# Shield-Proteco.net
KiCad netlist of a schematic drawn in EAGLE
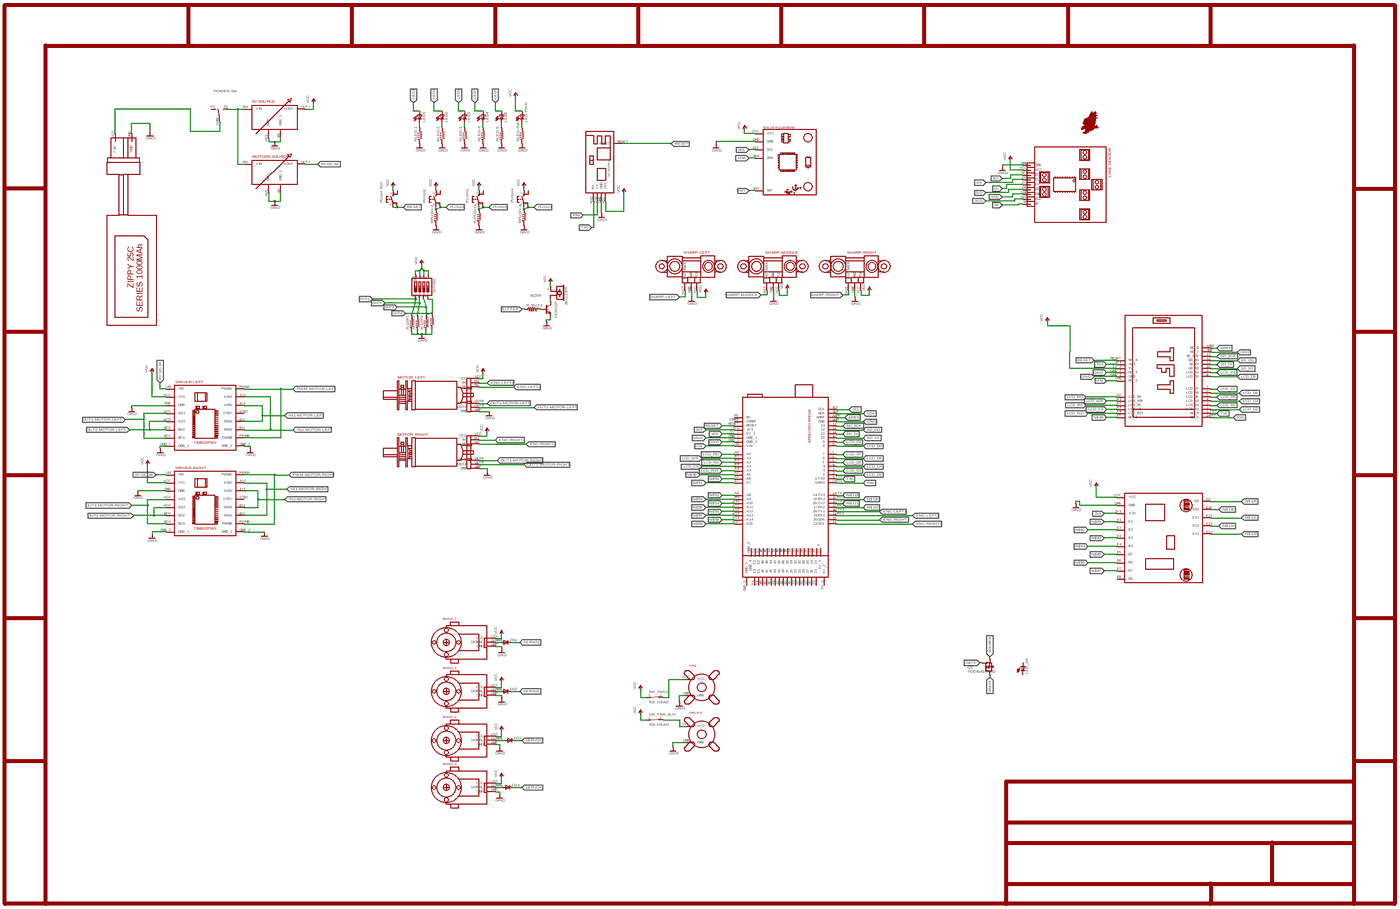
[diagram p0: schematic, sheet 1, overview]
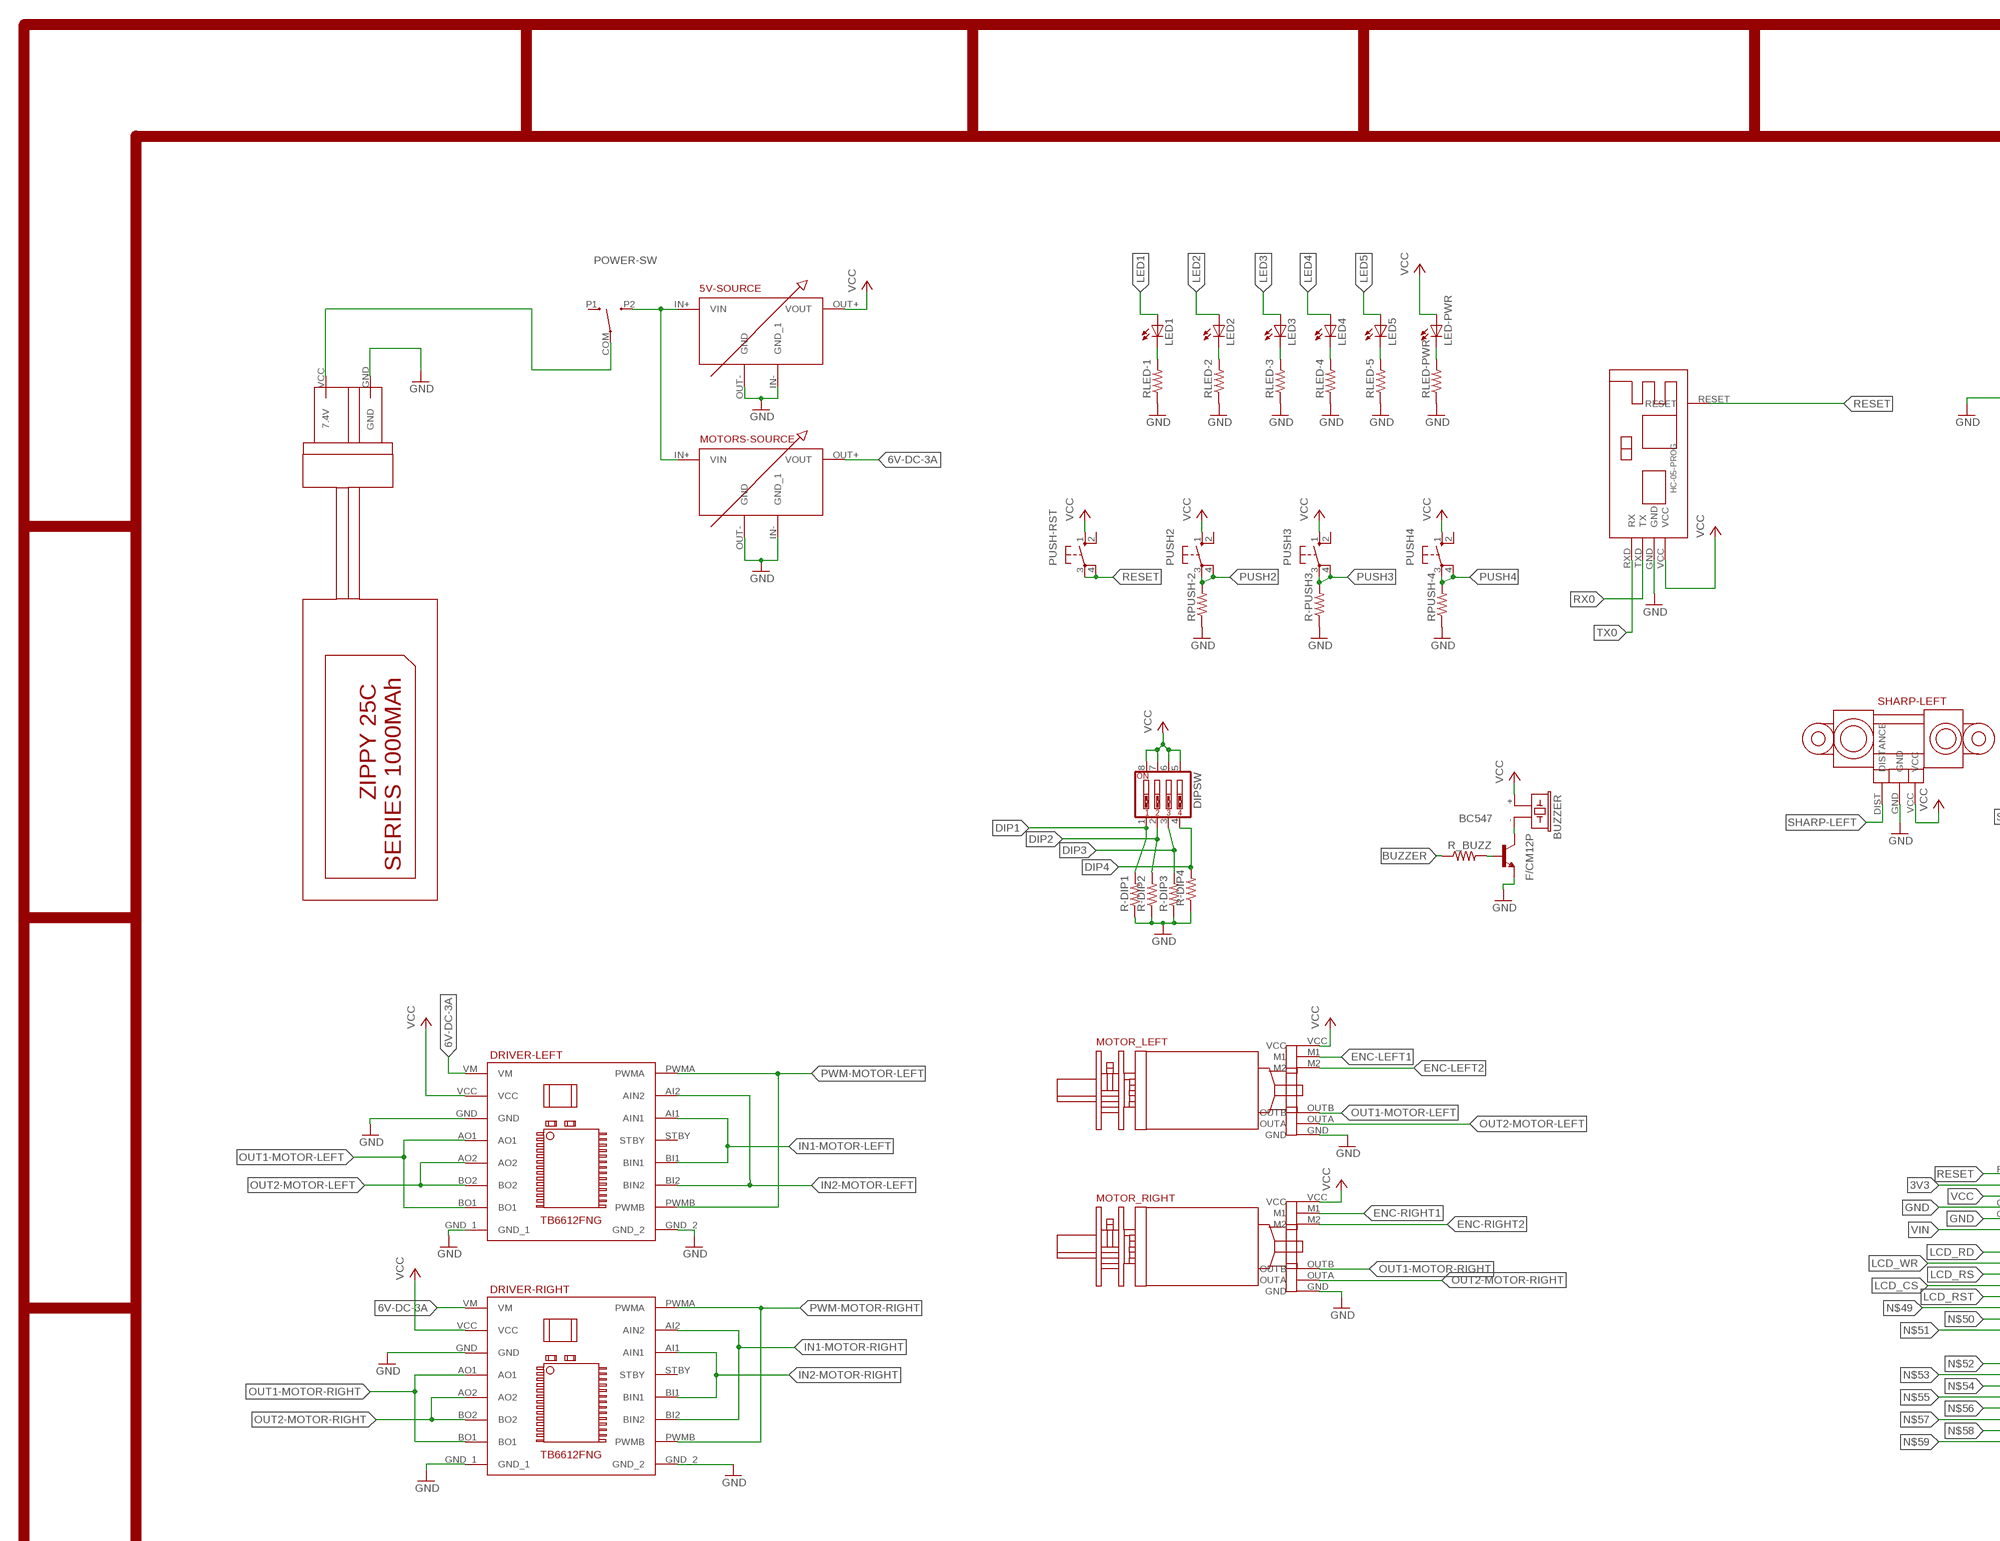
[diagram p1: schematic, sheet 1, part 1 of 4]
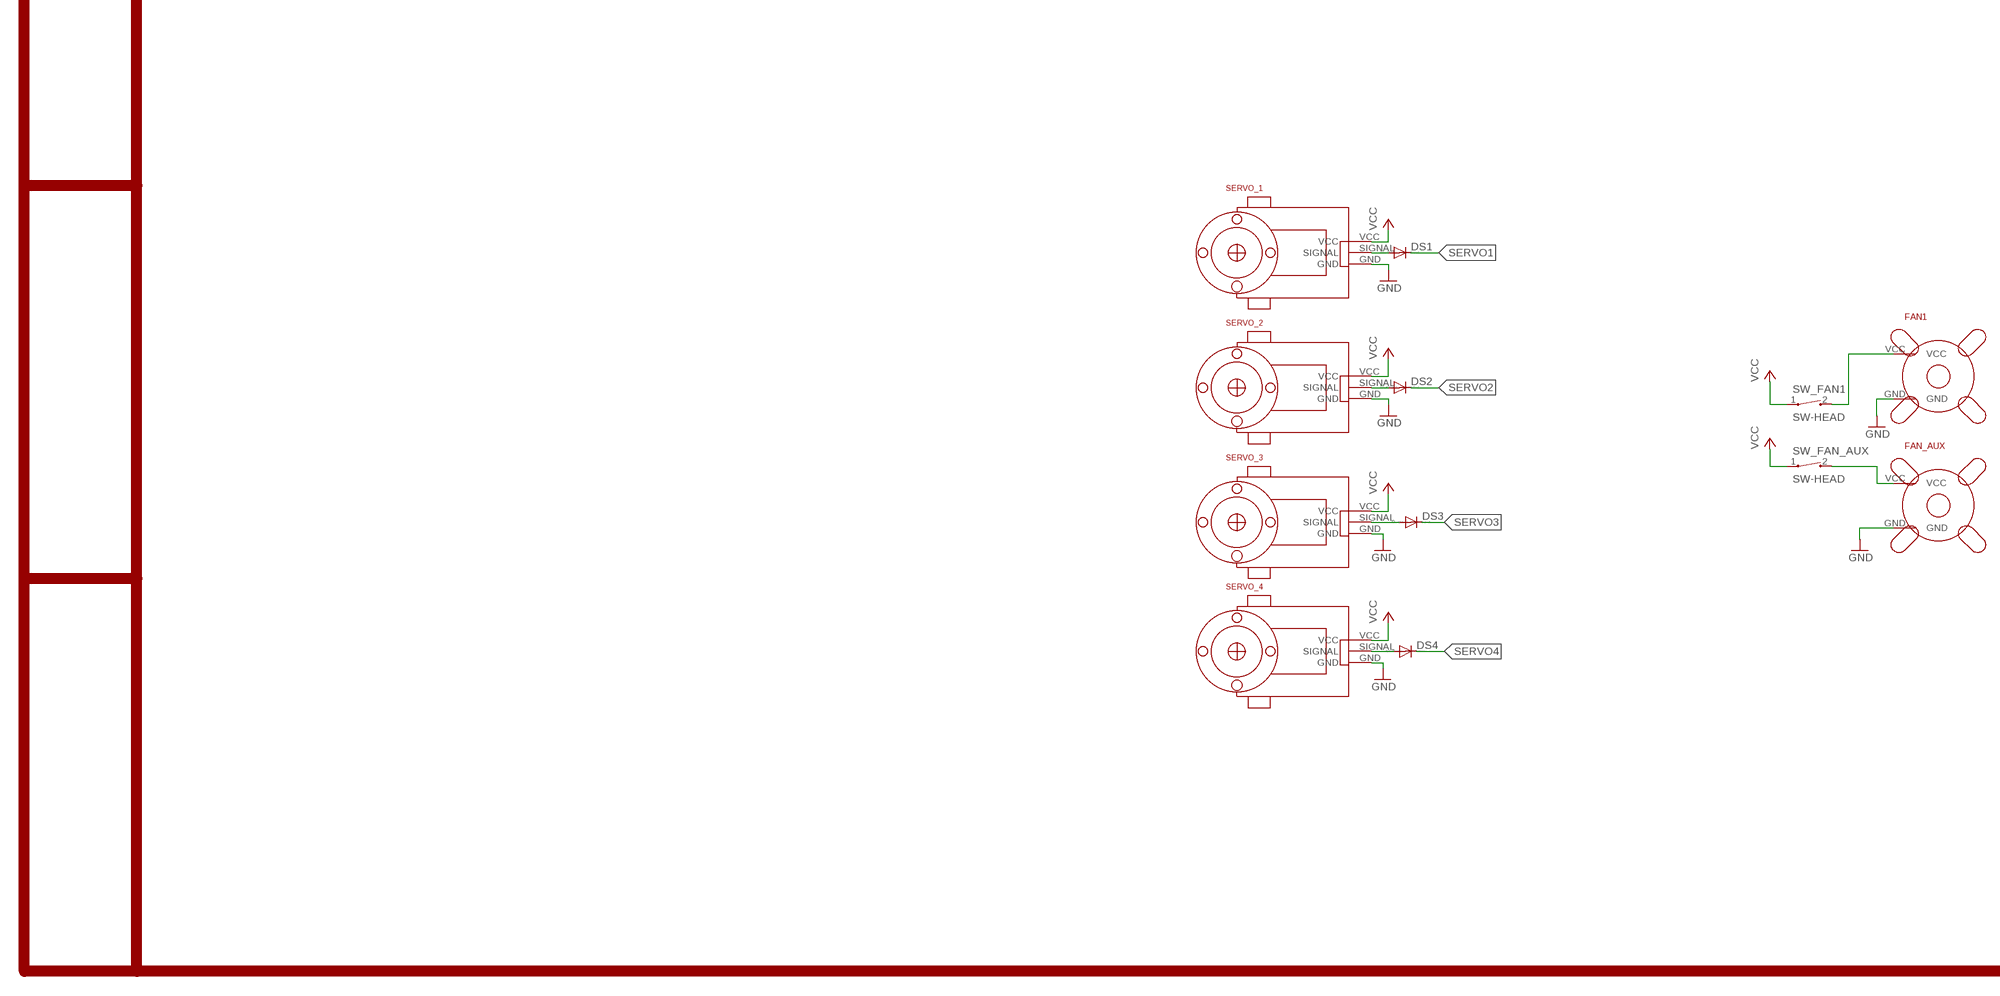
[diagram p2: schematic, sheet 1, part 2 of 4]
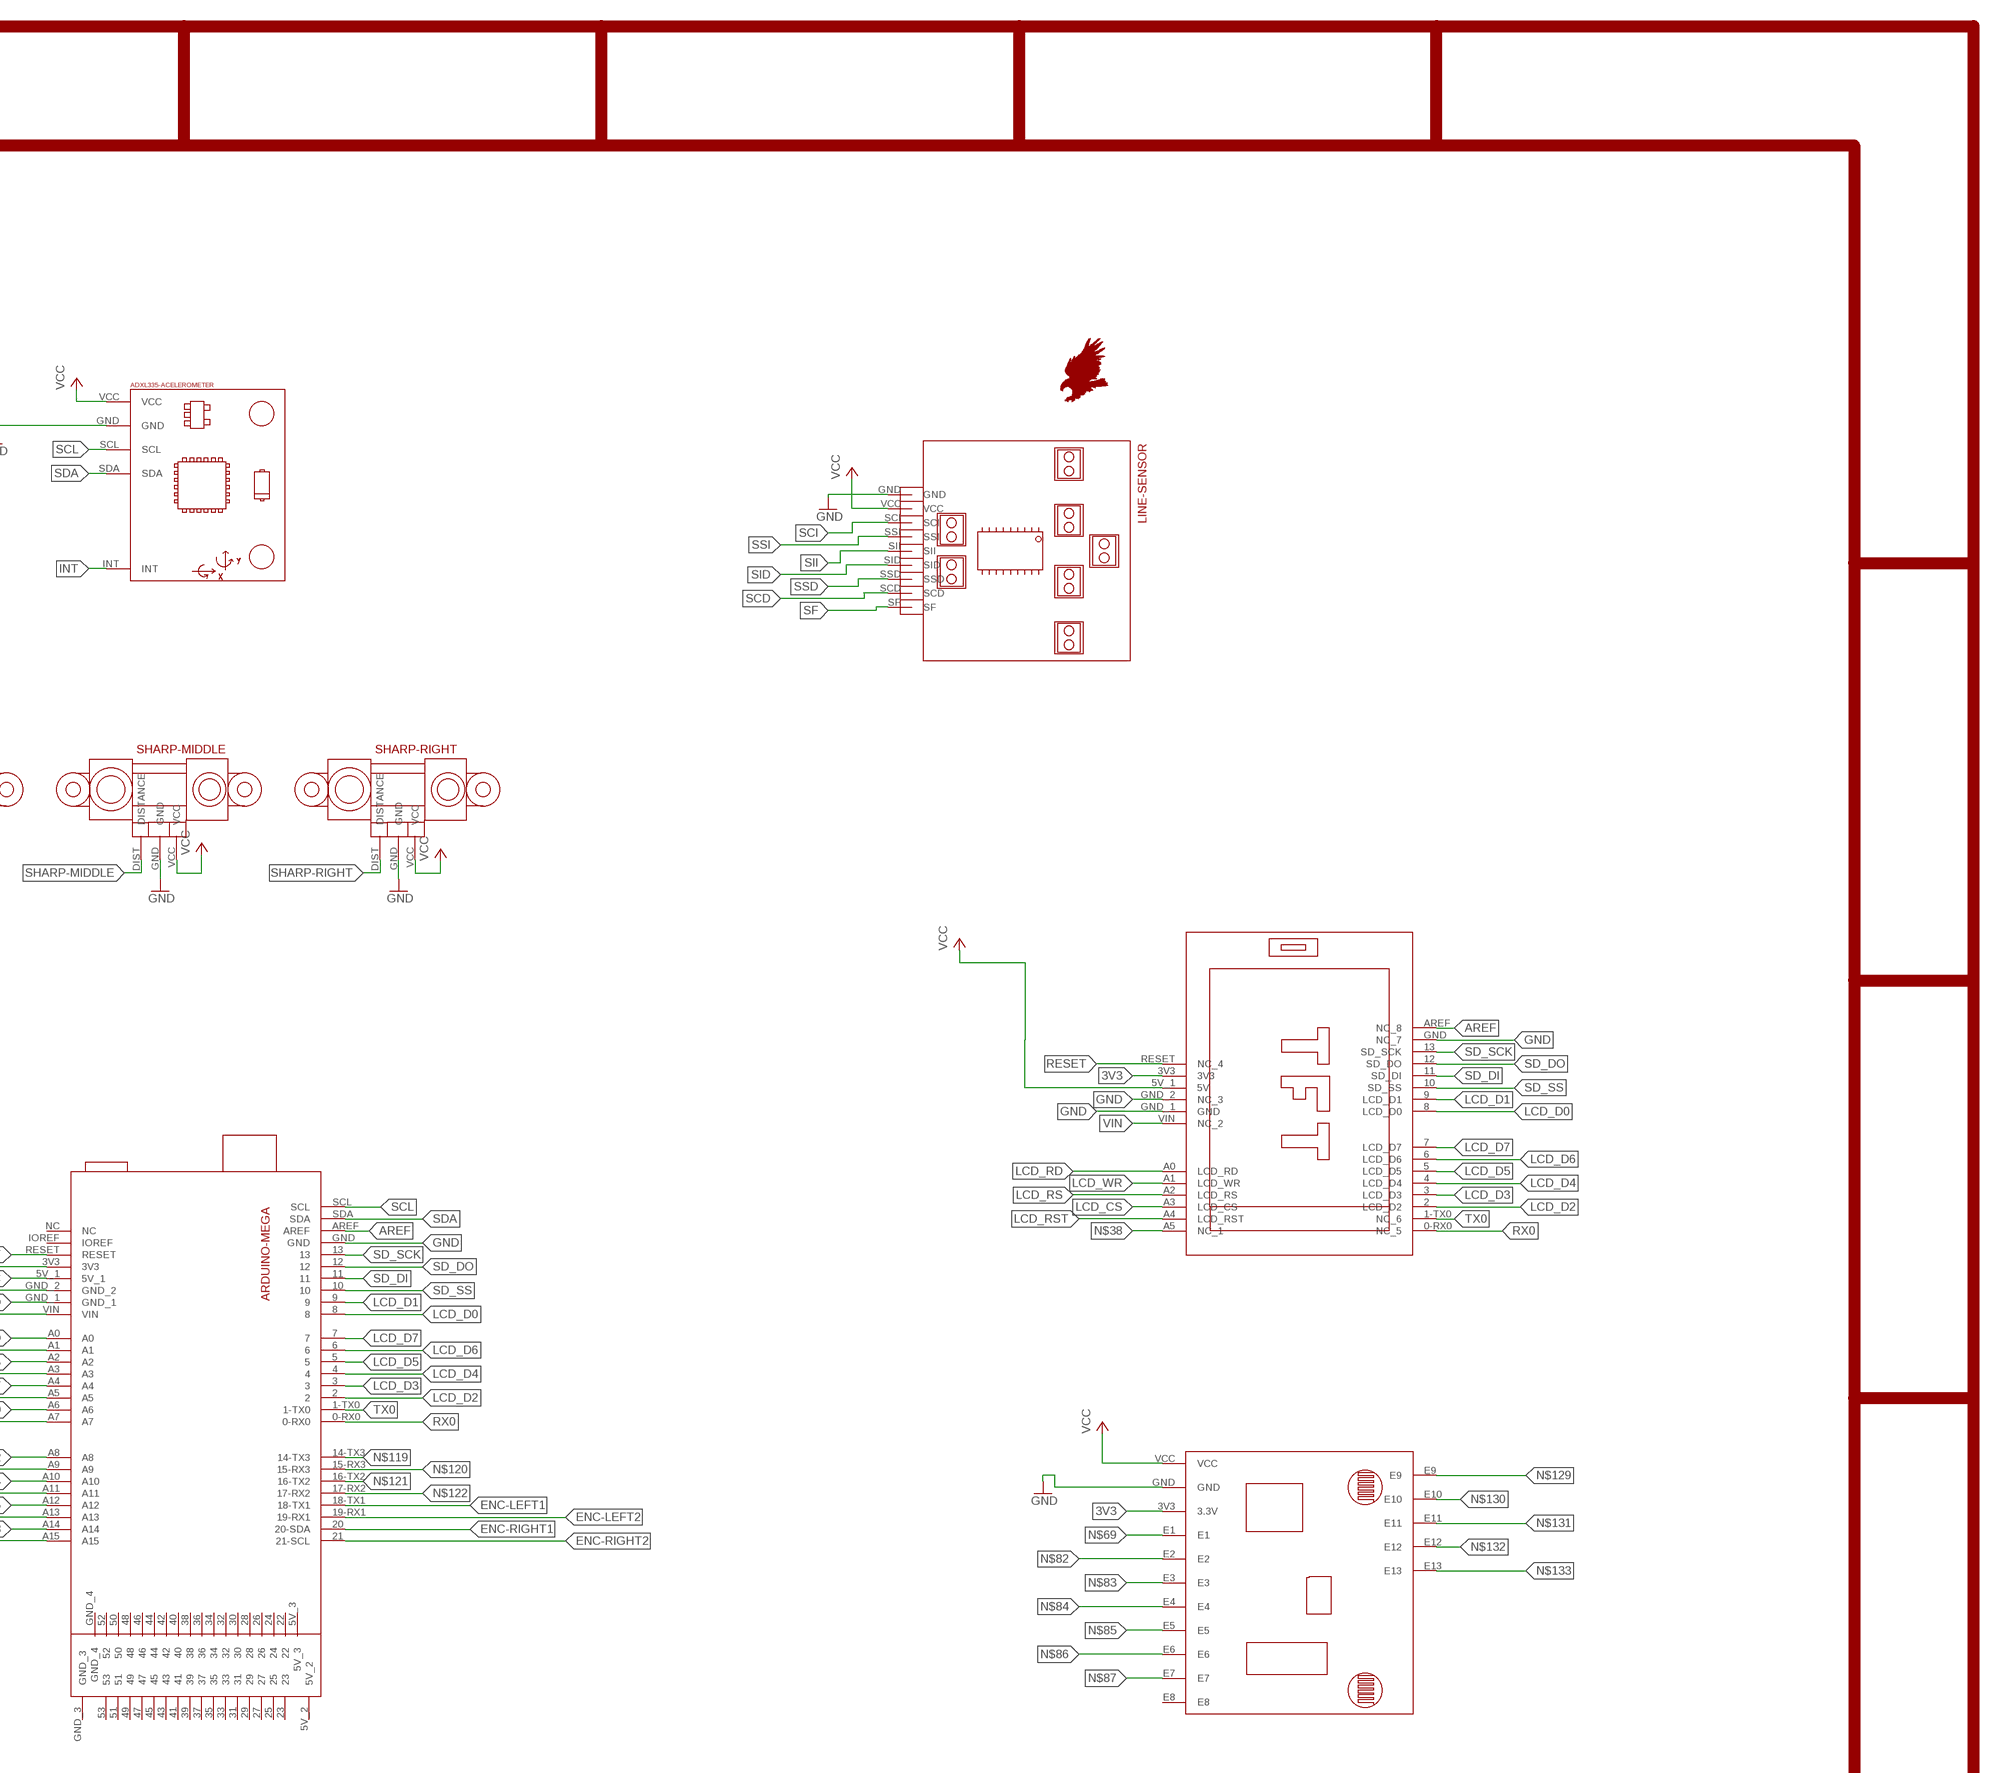
[diagram p3: schematic, sheet 1, part 3 of 4]
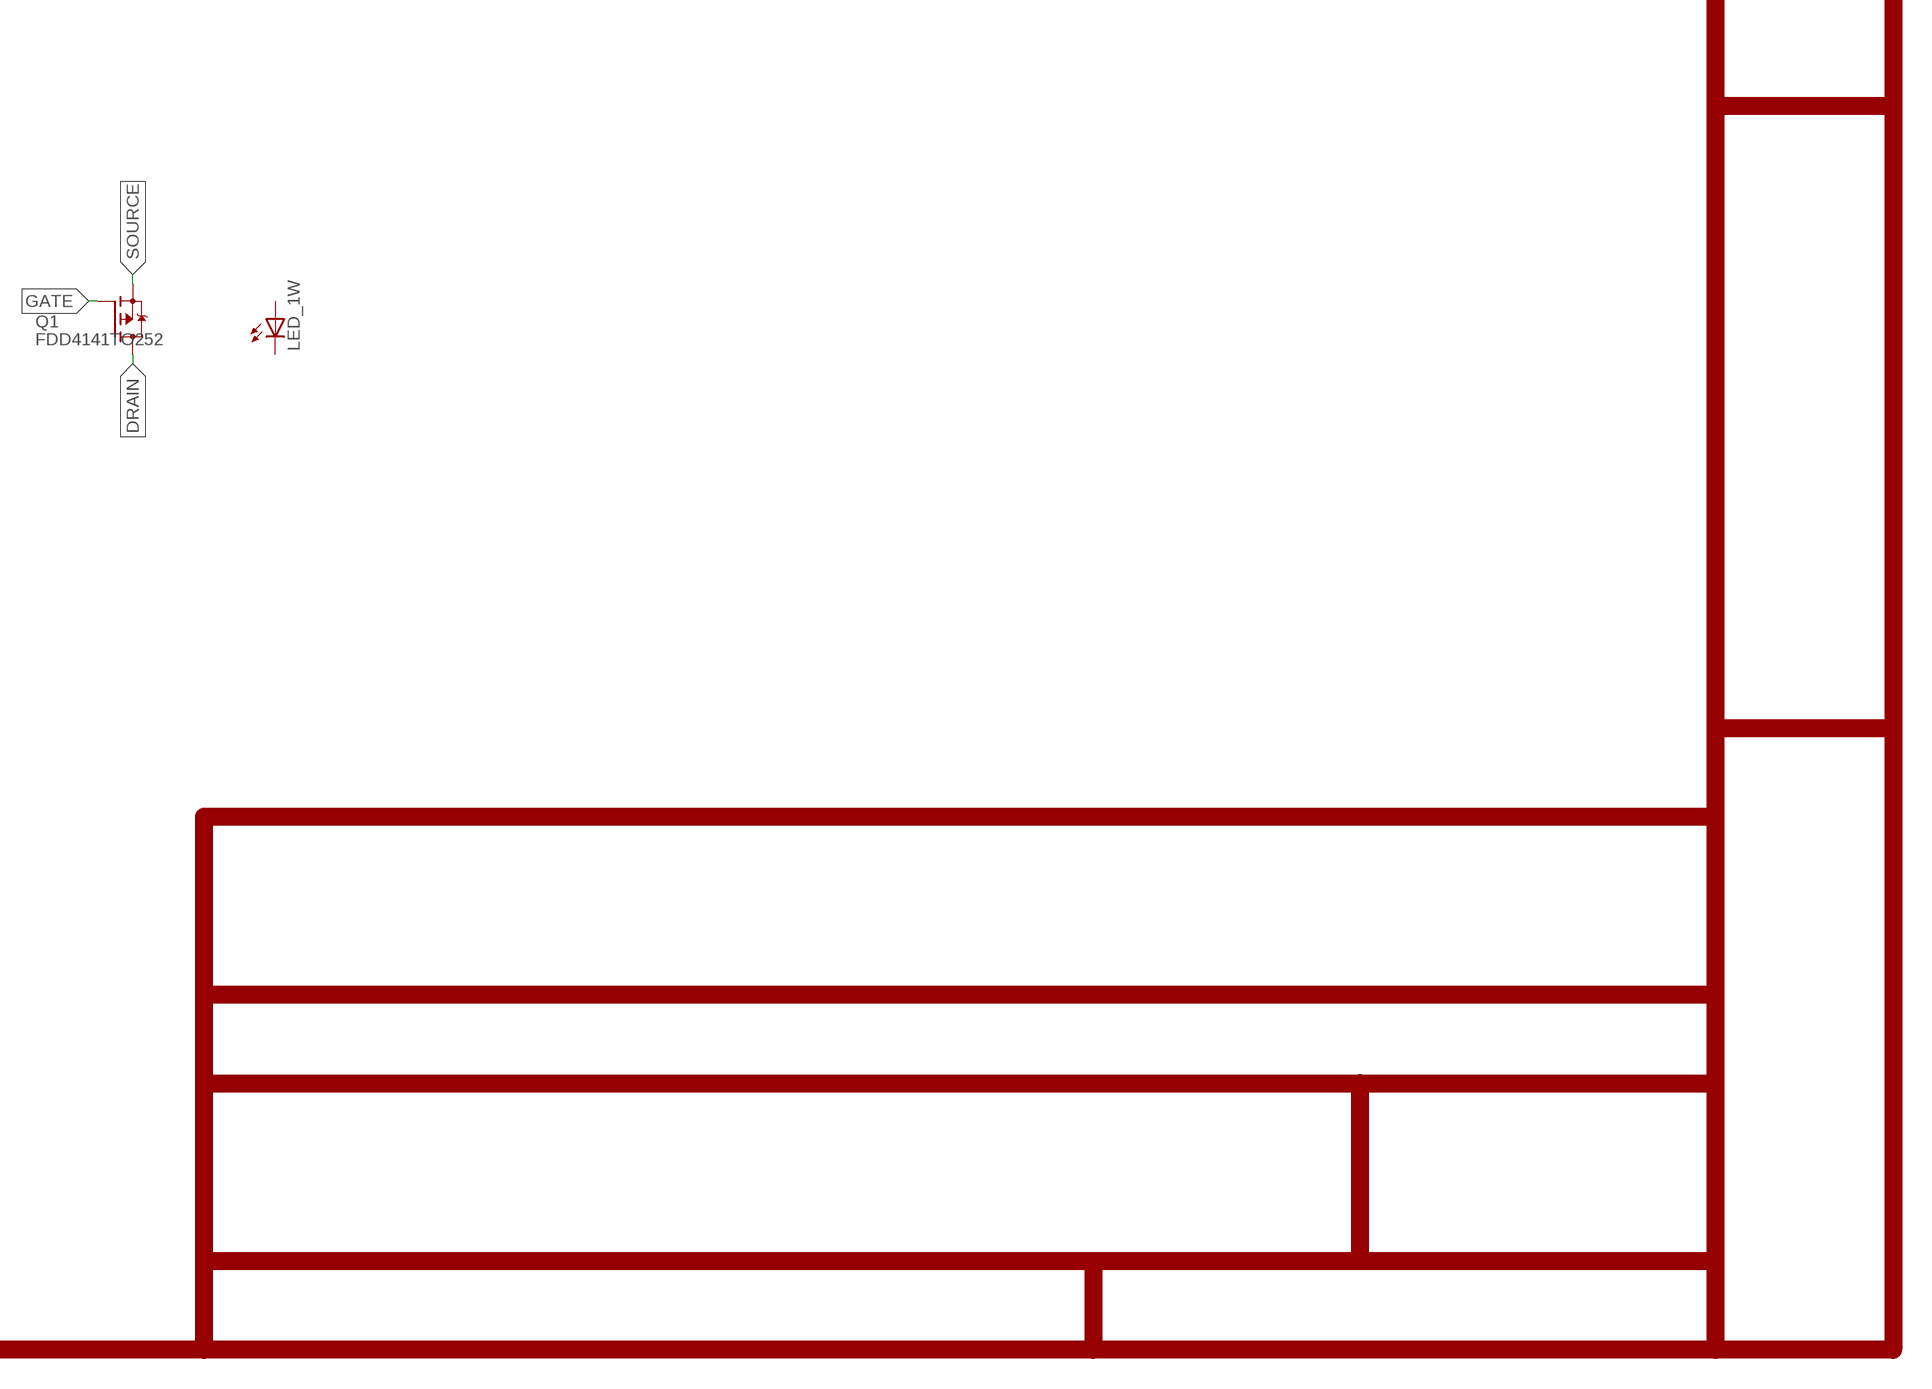
[diagram p4: schematic, sheet 1, part 4 of 4]

(export (version "E")
  (design (tool "Eeschema 10.0.6"))
  (components
    (comp (ref "5V-SOURCE")
      (value "STEPDOWN-DC-DC")
      (footprint "eagle-import:STEPDOWN-DC-DC")
      (libsource (lib "eagle-import") (part "STEPDOWN-DC-DC"))
    )
    (comp (ref "ADXL335-ACELEROMETER")
      (value "ACELEROMETER-JST-5")
      (footprint "eagle-import:ACELEROMETER-MPU6050-JST-5")
      (libsource (lib "eagle-import") (part "ACELEROMETER-JST-5"))
    )
    (comp (ref "ARDUINO-MEGA")
      (value "ARDUINO_MEGA")
      (footprint "eagle-import:ARDUINO-MEGA")
      (libsource (lib "eagle-import") (part "ARDUINO_MEGA"))
    )
    (comp (ref "BC547")
      (value "BC547-NPN-TO92-CBE")
      (footprint "eagle-import:TO92-CBE")
      (libsource (lib "eagle-import") (part "-NPN-TO92-CBEBC547"))
    )
    (comp (ref "BUZZER")
      (value "F/CM12P")
      (footprint "eagle-import:F_CM12P")
      (libsource (lib "eagle-import") (part "F/CM12P"))
    )
    (comp (ref "DIPSW")
      (value "SW_DIP-4")
      (footprint "eagle-import:EDG-04")
      (libsource (lib "eagle-import") (part "SW_DIP-4"))
    )
    (comp (ref "DRIVER-LEFT")
      (value "TB6612FNG")
      (footprint "eagle-import:TB6612FNG")
      (libsource (lib "eagle-import") (part "TB6612FNG"))
    )
    (comp (ref "DRIVER-RIGHT")
      (value "TB6612FNG")
      (footprint "eagle-import:TB6612FNG")
      (libsource (lib "eagle-import") (part "TB6612FNG"))
    )
    (comp (ref "DS1")
      (value "DIODE-DO-214AC")
      (footprint "eagle-import:DO-214AC")
      (libsource (lib "eagle-import") (part "DIODE-DO-214AC"))
    )
    (comp (ref "DS2")
      (value "DIODE-DO-214AC")
      (footprint "eagle-import:DO-214AC")
      (libsource (lib "eagle-import") (part "DIODE-DO-214AC"))
    )
    (comp (ref "DS3")
      (value "DIODE-DO-214AC")
      (footprint "eagle-import:DO-214AC")
      (libsource (lib "eagle-import") (part "DIODE-DO-214AC"))
    )
    (comp (ref "DS4")
      (value "DIODE-DO-214AC")
      (footprint "eagle-import:DO-214AC")
      (libsource (lib "eagle-import") (part "DIODE-DO-214AC"))
    )
    (comp (ref "FAN1")
      (value "FAN-MOLEX")
      (footprint "eagle-import:1X02")
      (libsource (lib "eagle-import") (part "FAN-MOLEX"))
    )
    (comp (ref "FAN_AUX")
      (value "FAN-MOLEX")
      (footprint "eagle-import:1X02")
      (libsource (lib "eagle-import") (part "FAN-MOLEX"))
    )
    (comp (ref "HC-05-PROG")
      (value "HC-05-PROGRAMER")
      (footprint "eagle-import:HC-05-PROG-COMP")
      (libsource (lib "eagle-import") (part "HC-05-PROGRAMER"))
    )
    (comp (ref "LED-PWR")
      (value "LEDCHIPLED_1206")
      (footprint "eagle-import:CHIPLED_1206")
      (libsource (lib "eagle-import") (part "LEDCHIPLED_1206"))
    )
    (comp (ref "LED1")
      (value "LEDCHIPLED_1206")
      (footprint "eagle-import:CHIPLED_1206")
      (libsource (lib "eagle-import") (part "LEDCHIPLED_1206"))
    )
    (comp (ref "LED2")
      (value "LEDCHIPLED_1206")
      (footprint "eagle-import:CHIPLED_1206")
      (libsource (lib "eagle-import") (part "LEDCHIPLED_1206"))
    )
    (comp (ref "LED3")
      (value "LEDCHIPLED_1206")
      (footprint "eagle-import:CHIPLED_1206")
      (libsource (lib "eagle-import") (part "LEDCHIPLED_1206"))
    )
    (comp (ref "LED4")
      (value "LEDCHIPLED_1206")
      (footprint "eagle-import:CHIPLED_1206")
      (libsource (lib "eagle-import") (part "LEDCHIPLED_1206"))
    )
    (comp (ref "LED5")
      (value "LEDCHIPLED_1206")
      (footprint "eagle-import:CHIPLED_1206")
      (libsource (lib "eagle-import") (part "LEDCHIPLED_1206"))
    )
    (comp (ref "LED_1W")
      (value "LED-1W-3V3")
      (footprint "eagle-import:1X02")
      (libsource (lib "eagle-import") (part "LED-1W-3V3"))
    )
    (comp (ref "LINE-SENSOR")
      (value "CNY70-ARRAY-HEADER")
      (footprint "eagle-import:CNY70-ARRAY-HEADER")
      (libsource (lib "eagle-import") (part "CNY70-ARRAY-HEADER"))
    )
    (comp (ref "MOTORS-SOURCE")
      (value "STEPDOWN-DC-DC")
      (footprint "eagle-import:STEPDOWN-DC-DC")
      (libsource (lib "eagle-import") (part "STEPDOWN-DC-DC"))
    )
    (comp (ref "MOTOR_LEFT")
      (value "POLOLU-MICROMOTOR")
      (footprint "eagle-import:JST")
      (libsource (lib "eagle-import") (part "POLOLU-MICROMOTOR"))
    )
    (comp (ref "MOTOR_RIGHT")
      (value "POLOLU-MICROMOTOR")
      (footprint "eagle-import:JST")
      (libsource (lib "eagle-import") (part "POLOLU-MICROMOTOR"))
    )
    (comp (ref "POWER-SW")
      (value "SLIDE-3")
      (footprint "eagle-import:SLIDE-3")
      (libsource (lib "eagle-import") (part "SLIDE-3"))
    )
    (comp (ref "PUSH-RST")
      (value "10-XX")
      (footprint "eagle-import:B3F-10XX")
      (fields (field (name "MPN") "B3F-1000"))
      (libsource (lib "eagle-import") (part "10-XX"))
    )
    (comp (ref "PUSH2")
      (value "10-XX")
      (footprint "eagle-import:B3F-10XX")
      (fields (field (name "MPN") "B3F-1000"))
      (libsource (lib "eagle-import") (part "10-XX"))
    )
    (comp (ref "PUSH3")
      (value "10-XX")
      (footprint "eagle-import:B3F-10XX")
      (fields (field (name "MPN") "B3F-1000"))
      (libsource (lib "eagle-import") (part "10-XX"))
    )
    (comp (ref "PUSH4")
      (value "10-XX")
      (footprint "eagle-import:B3F-10XX")
      (fields (field (name "MPN") "B3F-1000"))
      (libsource (lib "eagle-import") (part "10-XX"))
    )
    (comp (ref "Q1")
      (value "FDD4141TO252")
      (footprint "eagle-import:TO252")
      (libsource (lib "eagle-import") (part "FDD4141TO252"))
    )
    (comp (ref "R-DIP1")
      (value "R-US_M1206")
      (footprint "eagle-import:M1206")
      (libsource (lib "eagle-import") (part "R-US_M1206"))
    )
    (comp (ref "R-DIP2")
      (value "R-US_M1206")
      (footprint "eagle-import:M1206")
      (libsource (lib "eagle-import") (part "R-US_M1206"))
    )
    (comp (ref "R-DIP3")
      (value "R-US_M1206")
      (footprint "eagle-import:M1206")
      (libsource (lib "eagle-import") (part "R-US_M1206"))
    )
    (comp (ref "R-DIP4")
      (value "R-US_M1206")
      (footprint "eagle-import:M1206")
      (libsource (lib "eagle-import") (part "R-US_M1206"))
    )
    (comp (ref "R-PUSH3")
      (value "R-US_M1206")
      (footprint "eagle-import:M1206")
      (libsource (lib "eagle-import") (part "R-US_M1206"))
    )
    (comp (ref "RLED-1")
      (value "R-US_M1206")
      (footprint "eagle-import:M1206")
      (libsource (lib "eagle-import") (part "R-US_M1206"))
    )
    (comp (ref "RLED-2")
      (value "R-US_M1206")
      (footprint "eagle-import:M1206")
      (libsource (lib "eagle-import") (part "R-US_M1206"))
    )
    (comp (ref "RLED-3")
      (value "R-US_M1206")
      (footprint "eagle-import:M1206")
      (libsource (lib "eagle-import") (part "R-US_M1206"))
    )
    (comp (ref "RLED-4")
      (value "R-US_M1206")
      (footprint "eagle-import:M1206")
      (libsource (lib "eagle-import") (part "R-US_M1206"))
    )
    (comp (ref "RLED-5")
      (value "R-US_M1206")
      (footprint "eagle-import:M1206")
      (libsource (lib "eagle-import") (part "R-US_M1206"))
    )
    (comp (ref "RLED-PWR")
      (value "R-US_M1206")
      (footprint "eagle-import:M1206")
      (libsource (lib "eagle-import") (part "R-US_M1206"))
    )
    (comp (ref "RPUSH-2")
      (value "R-US_M1206")
      (footprint "eagle-import:M1206")
      (libsource (lib "eagle-import") (part "R-US_M1206"))
    )
    (comp (ref "RPUSH-4")
      (value "R-US_M1206")
      (footprint "eagle-import:M1206")
      (libsource (lib "eagle-import") (part "R-US_M1206"))
    )
    (comp (ref "R_BUZZ")
      (value "R-US_M1206")
      (footprint "eagle-import:M1206")
      (libsource (lib "eagle-import") (part "R-US_M1206"))
    )
    (comp (ref "SERVO_1")
      (value "SERVOMOTORES")
      (footprint "eagle-import:SERVO")
      (libsource (lib "eagle-import") (part "SERVOMOTORES"))
    )
    (comp (ref "SERVO_2")
      (value "SERVOMOTORES")
      (footprint "eagle-import:SERVO")
      (libsource (lib "eagle-import") (part "SERVOMOTORES"))
    )
    (comp (ref "SERVO_3")
      (value "SERVOMOTORES")
      (footprint "eagle-import:SERVO")
      (libsource (lib "eagle-import") (part "SERVOMOTORES"))
    )
    (comp (ref "SERVO_4")
      (value "SERVOMOTORES")
      (footprint "eagle-import:SERVO")
      (libsource (lib "eagle-import") (part "SERVOMOTORES"))
    )
    (comp (ref "SHARP-LEFT")
      (value "SHARP")
      (footprint "eagle-import:SHARP")
      (libsource (lib "eagle-import") (part "SHARP"))
    )
    (comp (ref "SHARP-MIDDLE")
      (value "SHARP")
      (footprint "eagle-import:SHARP")
      (libsource (lib "eagle-import") (part "SHARP"))
    )
    (comp (ref "SHARP-RIGHT")
      (value "SHARP")
      (footprint "eagle-import:SHARP")
      (libsource (lib "eagle-import") (part "SHARP"))
    )
    (comp (ref "SW_FAN1")
      (value "SW-HEAD")
      (footprint "eagle-import:1X02")
      (libsource (lib "eagle-import") (part "SW-HEAD"))
    )
    (comp (ref "SW_FAN_AUX")
      (value "SW-HEAD")
      (footprint "eagle-import:1X02")
      (libsource (lib "eagle-import") (part "SW-HEAD"))
    )
    (comp (ref "U$9")
      (value "SENSOR-MISCELANEOUS")
      (footprint "eagle-import:SENSOR-MISCELANEOUS")
      (libsource (lib "eagle-import") (part "SENSOR-MISCELANEOUS"))
    )
    (comp (ref "U$14")
      (value "TFT_ARDUINO-UNO-MEGA")
      (footprint "eagle-import:TFT-ARDUINO-UNO-MEGA")
      (libsource (lib "eagle-import") (part "TFT_ARDUINO-UNO-MEGA"))
    )
    (comp (ref "U$23")
      (value "ZIIPY-7.4V")
      (footprint "eagle-import:XT60")
      (libsource (lib "eagle-import") (part "ZIIPY-7.4V"))
    )
  )
  (nets
    (net (code "1") (name "3V3") (class "Default")
      (node (ref "ARDUINO-MEGA") (pin "3V3") (pinfunction "3V3_3V3") (pintype "bidirectional"))
      (node (ref "U$14") (pin "3V3") (pinfunction "3V3_3V3") (pintype "bidirectional"))
      (node (ref "U$9") (pin "3V3") (pinfunction "3.3V_3V3") (pintype "bidirectional"))
    )
    (net (code "2") (name "6V-DC-3A") (class "Default")
      (node (ref "DRIVER-LEFT") (pin "VM") (pinfunction "VM_VM") (pintype "bidirectional"))
      (node (ref "DRIVER-RIGHT") (pin "VM") (pinfunction "VM_VM") (pintype "bidirectional"))
      (node (ref "MOTORS-SOURCE") (pin "OUT+") (pinfunction "VOUT_OUT+") (pintype "bidirectional"))
    )
    (net (code "3") (name "AREF") (class "Default")
      (node (ref "ARDUINO-MEGA") (pin "AREF") (pinfunction "AREF_AREF") (pintype "bidirectional"))
      (node (ref "U$14") (pin "AREF") (pinfunction "NC_8_AREF") (pintype "bidirectional"))
    )
    (net (code "4") (name "BUZZER") (class "Default")
      (node (ref "R_BUZZ") (pin "1") (pinfunction "1_1") (pintype "passive"))
    )
    (net (code "5") (name "DIP1") (class "Default")
      (node (ref "DIPSW") (pin "1") (pinfunction "1_1") (pintype "passive"))
      (node (ref "R-DIP1") (pin "2") (pinfunction "2_2") (pintype "passive"))
    )
    (net (code "6") (name "DIP2") (class "Default")
      (node (ref "DIPSW") (pin "2") (pinfunction "2_2") (pintype "passive"))
      (node (ref "R-DIP2") (pin "2") (pinfunction "2_2") (pintype "passive"))
    )
    (net (code "7") (name "DIP3") (class "Default")
      (node (ref "DIPSW") (pin "3") (pinfunction "3_3") (pintype "passive"))
      (node (ref "R-DIP3") (pin "2") (pinfunction "2_2") (pintype "passive"))
    )
    (net (code "8") (name "DIP4") (class "Default")
      (node (ref "DIPSW") (pin "4") (pinfunction "4_4") (pintype "passive"))
      (node (ref "R-DIP4") (pin "2") (pinfunction "2_2") (pintype "passive"))
    )
    (net (code "9") (name "DRAIN") (class "Default")
      (node (ref "Q1") (pin "3") (pinfunction "D_3") (pintype "passive"))
    )
    (net (code "10") (name "ENC-LEFT1") (class "Default")
      (node (ref "ARDUINO-MEGA") (pin "18-TX1") (pinfunction "18-TX1_18-TX1") (pintype "bidirectional"))
      (node (ref "MOTOR_LEFT") (pin "M1") (pinfunction "M1_M1") (pintype "bidirectional"))
    )
    (net (code "11") (name "ENC-LEFT2") (class "Default")
      (node (ref "ARDUINO-MEGA") (pin "19-RX1") (pinfunction "19-RX1_19-RX1") (pintype "bidirectional"))
      (node (ref "MOTOR_LEFT") (pin "M2") (pinfunction "M2_M2") (pintype "bidirectional"))
    )
    (net (code "12") (name "ENC-RIGHT1") (class "Default")
      (node (ref "ARDUINO-MEGA") (pin "20") (pinfunction "20-SDA_20") (pintype "bidirectional"))
      (node (ref "MOTOR_RIGHT") (pin "M1") (pinfunction "M1_M1") (pintype "bidirectional"))
    )
    (net (code "13") (name "ENC-RIGHT2") (class "Default")
      (node (ref "ARDUINO-MEGA") (pin "21") (pinfunction "21-SCL_21") (pintype "bidirectional"))
      (node (ref "MOTOR_RIGHT") (pin "M2") (pinfunction "M2_M2") (pintype "bidirectional"))
    )
    (net (code "14") (name "GATE") (class "Default")
      (node (ref "Q1") (pin "1") (pinfunction "G_1") (pintype "passive"))
    )
    (net (code "15") (name "GND") (class "Default")
      (node (ref "5V-SOURCE") (pin "IN-") (pinfunction "GND_1_IN-") (pintype "bidirectional"))
      (node (ref "5V-SOURCE") (pin "OUT-") (pinfunction "GND_OUT-") (pintype "bidirectional"))
      (node (ref "ADXL335-ACELEROMETER") (pin "GND") (pinfunction "GND_GND") (pintype "bidirectional"))
      (node (ref "ARDUINO-MEGA") (pin "GND") (pinfunction "GND_GND") (pintype "bidirectional"))
      (node (ref "ARDUINO-MEGA") (pin "GND_1") (pinfunction "GND_1_GND_1") (pintype "bidirectional"))
      (node (ref "ARDUINO-MEGA") (pin "GND_2") (pinfunction "GND_2_GND_2") (pintype "bidirectional"))
      (node (ref "BC547") (pin "E") (pinfunction "E_E") (pintype "passive"))
      (node (ref "DRIVER-LEFT") (pin "GND") (pinfunction "GND_GND") (pintype "bidirectional"))
      (node (ref "DRIVER-LEFT") (pin "GND_1") (pinfunction "GND_1_GND_1") (pintype "bidirectional"))
      (node (ref "DRIVER-LEFT") (pin "GND_2") (pinfunction "GND_2_GND_2") (pintype "bidirectional"))
      (node (ref "DRIVER-RIGHT") (pin "GND") (pinfunction "GND_GND") (pintype "bidirectional"))
      (node (ref "DRIVER-RIGHT") (pin "GND_1") (pinfunction "GND_1_GND_1") (pintype "bidirectional"))
      (node (ref "DRIVER-RIGHT") (pin "GND_2") (pinfunction "GND_2_GND_2") (pintype "bidirectional"))
      (node (ref "FAN1") (pin "GND") (pinfunction "GND_GND") (pintype "bidirectional"))
      (node (ref "FAN_AUX") (pin "GND") (pinfunction "GND_GND") (pintype "bidirectional"))
      (node (ref "HC-05-PROG") (pin "GND") (pinfunction "GND_GND") (pintype "bidirectional"))
      (node (ref "LINE-SENSOR") (pin "GND") (pinfunction "GND_GND") (pintype "bidirectional"))
      (node (ref "MOTORS-SOURCE") (pin "IN-") (pinfunction "GND_1_IN-") (pintype "bidirectional"))
      (node (ref "MOTORS-SOURCE") (pin "OUT-") (pinfunction "GND_OUT-") (pintype "bidirectional"))
      (node (ref "MOTOR_LEFT") (pin "GND") (pinfunction "GND_GND") (pintype "bidirectional"))
      (node (ref "MOTOR_RIGHT") (pin "GND") (pinfunction "GND_GND") (pintype "bidirectional"))
      (node (ref "R-DIP1") (pin "1") (pinfunction "1_1") (pintype "passive"))
      (node (ref "R-DIP2") (pin "1") (pinfunction "1_1") (pintype "passive"))
      (node (ref "R-DIP3") (pin "1") (pinfunction "1_1") (pintype "passive"))
      (node (ref "R-DIP4") (pin "1") (pinfunction "1_1") (pintype "passive"))
      (node (ref "R-PUSH3") (pin "1") (pinfunction "1_1") (pintype "passive"))
      (node (ref "RLED-1") (pin "1") (pinfunction "1_1") (pintype "passive"))
      (node (ref "RLED-2") (pin "1") (pinfunction "1_1") (pintype "passive"))
      (node (ref "RLED-3") (pin "1") (pinfunction "1_1") (pintype "passive"))
      (node (ref "RLED-4") (pin "1") (pinfunction "1_1") (pintype "passive"))
      (node (ref "RLED-5") (pin "1") (pinfunction "1_1") (pintype "passive"))
      (node (ref "RLED-PWR") (pin "1") (pinfunction "1_1") (pintype "passive"))
      (node (ref "RPUSH-2") (pin "1") (pinfunction "1_1") (pintype "passive"))
      (node (ref "RPUSH-4") (pin "1") (pinfunction "1_1") (pintype "passive"))
      (node (ref "SERVO_1") (pin "GND") (pinfunction "GND_GND") (pintype "bidirectional"))
      (node (ref "SERVO_2") (pin "GND") (pinfunction "GND_GND") (pintype "bidirectional"))
      (node (ref "SERVO_3") (pin "GND") (pinfunction "GND_GND") (pintype "bidirectional"))
      (node (ref "SERVO_4") (pin "GND") (pinfunction "GND_GND") (pintype "bidirectional"))
      (node (ref "SHARP-LEFT") (pin "GND") (pinfunction "GND_GND") (pintype "bidirectional"))
      (node (ref "SHARP-MIDDLE") (pin "GND") (pinfunction "GND_GND") (pintype "bidirectional"))
      (node (ref "SHARP-RIGHT") (pin "GND") (pinfunction "GND_GND") (pintype "bidirectional"))
      (node (ref "U$14") (pin "GND") (pinfunction "NC_7_GND") (pintype "bidirectional"))
      (node (ref "U$14") (pin "GND_1") (pinfunction "GND_GND_1") (pintype "bidirectional"))
      (node (ref "U$14") (pin "GND_2") (pinfunction "NC_3_GND_2") (pintype "bidirectional"))
      (node (ref "U$23") (pin "GND") (pinfunction "GND_GND") (pintype "bidirectional"))
      (node (ref "U$9") (pin "GND") (pinfunction "GND_GND") (pintype "bidirectional"))
    )
    (net (code "16") (name "IN1-MOTOR-LEFT") (class "Default")
      (node (ref "DRIVER-LEFT") (pin "AI1") (pinfunction "AIN1_AI1") (pintype "bidirectional"))
      (node (ref "DRIVER-LEFT") (pin "BI1") (pinfunction "BIN1_BI1") (pintype "bidirectional"))
    )
    (net (code "17") (name "IN1-MOTOR-RIGHT") (class "Default")
      (node (ref "DRIVER-RIGHT") (pin "AI2") (pinfunction "AIN2_AI2") (pintype "bidirectional"))
      (node (ref "DRIVER-RIGHT") (pin "BI2") (pinfunction "BIN2_BI2") (pintype "bidirectional"))
    )
    (net (code "18") (name "IN2-MOTOR-LEFT") (class "Default")
      (node (ref "DRIVER-LEFT") (pin "AI2") (pinfunction "AIN2_AI2") (pintype "bidirectional"))
      (node (ref "DRIVER-LEFT") (pin "BI2") (pinfunction "BIN2_BI2") (pintype "bidirectional"))
    )
    (net (code "19") (name "IN2-MOTOR-RIGHT") (class "Default")
      (node (ref "DRIVER-RIGHT") (pin "AI1") (pinfunction "AIN1_AI1") (pintype "bidirectional"))
      (node (ref "DRIVER-RIGHT") (pin "BI1") (pinfunction "BIN1_BI1") (pintype "bidirectional"))
    )
    (net (code "20") (name "INT") (class "Default")
      (node (ref "ADXL335-ACELEROMETER") (pin "INT") (pinfunction "INT_INT") (pintype "bidirectional"))
    )
    (net (code "21") (name "LCD_CS") (class "Default")
      (node (ref "ARDUINO-MEGA") (pin "A3") (pinfunction "A3_A3") (pintype "bidirectional"))
      (node (ref "U$14") (pin "A3") (pinfunction "LCD_CS_A3") (pintype "bidirectional"))
    )
    (net (code "22") (name "LCD_D0") (class "Default")
      (node (ref "ARDUINO-MEGA") (pin "8") (pinfunction "8_8") (pintype "bidirectional"))
      (node (ref "U$14") (pin "8") (pinfunction "LCD_D0_8") (pintype "bidirectional"))
    )
    (net (code "23") (name "LCD_D1") (class "Default")
      (node (ref "ARDUINO-MEGA") (pin "9") (pinfunction "9_9") (pintype "bidirectional"))
      (node (ref "U$14") (pin "9") (pinfunction "LCD_D1_9") (pintype "bidirectional"))
    )
    (net (code "24") (name "LCD_D2") (class "Default")
      (node (ref "ARDUINO-MEGA") (pin "2") (pinfunction "2_2") (pintype "bidirectional"))
      (node (ref "U$14") (pin "2") (pinfunction "LCD_D2_2") (pintype "bidirectional"))
    )
    (net (code "25") (name "LCD_D3") (class "Default")
      (node (ref "ARDUINO-MEGA") (pin "3") (pinfunction "3_3") (pintype "bidirectional"))
      (node (ref "U$14") (pin "3") (pinfunction "LCD_D3_3") (pintype "bidirectional"))
    )
    (net (code "26") (name "LCD_D4") (class "Default")
      (node (ref "ARDUINO-MEGA") (pin "4") (pinfunction "4_4") (pintype "bidirectional"))
      (node (ref "U$14") (pin "4") (pinfunction "LCD_D4_4") (pintype "bidirectional"))
    )
    (net (code "27") (name "LCD_D5") (class "Default")
      (node (ref "ARDUINO-MEGA") (pin "5") (pinfunction "5_5") (pintype "bidirectional"))
      (node (ref "U$14") (pin "5") (pinfunction "LCD_D5_5") (pintype "bidirectional"))
    )
    (net (code "28") (name "LCD_D6") (class "Default")
      (node (ref "ARDUINO-MEGA") (pin "6") (pinfunction "6_6") (pintype "bidirectional"))
      (node (ref "U$14") (pin "6") (pinfunction "LCD_D6_6") (pintype "bidirectional"))
    )
    (net (code "29") (name "LCD_D7") (class "Default")
      (node (ref "ARDUINO-MEGA") (pin "7") (pinfunction "7_7") (pintype "bidirectional"))
      (node (ref "U$14") (pin "7") (pinfunction "LCD_D7_7") (pintype "bidirectional"))
    )
    (net (code "30") (name "LCD_RD") (class "Default")
      (node (ref "ARDUINO-MEGA") (pin "A0") (pinfunction "A0_A0") (pintype "bidirectional"))
      (node (ref "U$14") (pin "A0") (pinfunction "LCD_RD_A0") (pintype "bidirectional"))
    )
    (net (code "31") (name "LCD_RS") (class "Default")
      (node (ref "ARDUINO-MEGA") (pin "A2") (pinfunction "A2_A2") (pintype "bidirectional"))
      (node (ref "U$14") (pin "A2") (pinfunction "LCD_RS_A2") (pintype "bidirectional"))
    )
    (net (code "32") (name "LCD_RST") (class "Default")
      (node (ref "ARDUINO-MEGA") (pin "A4") (pinfunction "A4_A4") (pintype "bidirectional"))
      (node (ref "U$14") (pin "A4") (pinfunction "LCD_RST_A4") (pintype "bidirectional"))
    )
    (net (code "33") (name "LCD_WR") (class "Default")
      (node (ref "ARDUINO-MEGA") (pin "A1") (pinfunction "A1_A1") (pintype "bidirectional"))
      (node (ref "U$14") (pin "A1") (pinfunction "LCD_WR_A1") (pintype "bidirectional"))
    )
    (net (code "34") (name "LED1") (class "Default")
      (node (ref "LED1") (pin "A") (pinfunction "A_A") (pintype "passive"))
    )
    (net (code "35") (name "LED2") (class "Default")
      (node (ref "LED2") (pin "A") (pinfunction "A_A") (pintype "passive"))
    )
    (net (code "36") (name "LED3") (class "Default")
      (node (ref "LED3") (pin "A") (pinfunction "A_A") (pintype "passive"))
    )
    (net (code "37") (name "LED4") (class "Default")
      (node (ref "LED4") (pin "A") (pinfunction "A_A") (pintype "passive"))
    )
    (net (code "38") (name "LED5") (class "Default")
      (node (ref "LED5") (pin "A") (pinfunction "A_A") (pintype "passive"))
    )
    (net (code "39") (name "N$38") (class "Default")
      (node (ref "U$14") (pin "A5") (pinfunction "NC_1_A5") (pintype "bidirectional"))
    )
    (net (code "40") (name "N$49") (class "Default")
      (node (ref "ARDUINO-MEGA") (pin "A5") (pinfunction "A5_A5") (pintype "bidirectional"))
    )
    (net (code "41") (name "N$50") (class "Default")
      (node (ref "ARDUINO-MEGA") (pin "A6") (pinfunction "A6_A6") (pintype "bidirectional"))
    )
    (net (code "42") (name "N$51") (class "Default")
      (node (ref "ARDUINO-MEGA") (pin "A7") (pinfunction "A7_A7") (pintype "bidirectional"))
    )
    (net (code "43") (name "N$52") (class "Default")
      (node (ref "ARDUINO-MEGA") (pin "A8") (pinfunction "A8_A8") (pintype "bidirectional"))
    )
    (net (code "44") (name "N$53") (class "Default")
      (node (ref "ARDUINO-MEGA") (pin "A9") (pinfunction "A9_A9") (pintype "bidirectional"))
    )
    (net (code "45") (name "N$54") (class "Default")
      (node (ref "ARDUINO-MEGA") (pin "A10") (pinfunction "A10_A10") (pintype "bidirectional"))
    )
    (net (code "46") (name "N$55") (class "Default")
      (node (ref "ARDUINO-MEGA") (pin "A11") (pinfunction "A11_A11") (pintype "bidirectional"))
    )
    (net (code "47") (name "N$56") (class "Default")
      (node (ref "ARDUINO-MEGA") (pin "A12") (pinfunction "A12_A12") (pintype "bidirectional"))
    )
    (net (code "48") (name "N$57") (class "Default")
      (node (ref "ARDUINO-MEGA") (pin "A13") (pinfunction "A13_A13") (pintype "bidirectional"))
    )
    (net (code "49") (name "N$58") (class "Default")
      (node (ref "ARDUINO-MEGA") (pin "A14") (pinfunction "A14_A14") (pintype "bidirectional"))
    )
    (net (code "50") (name "N$59") (class "Default")
      (node (ref "ARDUINO-MEGA") (pin "A15") (pinfunction "A15_A15") (pintype "bidirectional"))
    )
    (net (code "51") (name "N$69") (class "Default")
      (node (ref "U$9") (pin "E1") (pinfunction "E1_E1") (pintype "bidirectional"))
    )
    (net (code "52") (name "N$82") (class "Default")
      (node (ref "U$9") (pin "E2") (pinfunction "E2_E2") (pintype "bidirectional"))
    )
    (net (code "53") (name "N$83") (class "Default")
      (node (ref "U$9") (pin "E3") (pinfunction "E3_E3") (pintype "bidirectional"))
    )
    (net (code "54") (name "N$84") (class "Default")
      (node (ref "U$9") (pin "E4") (pinfunction "E4_E4") (pintype "bidirectional"))
    )
    (net (code "55") (name "N$85") (class "Default")
      (node (ref "U$9") (pin "E5") (pinfunction "E5_E5") (pintype "bidirectional"))
    )
    (net (code "56") (name "N$86") (class "Default")
      (node (ref "U$9") (pin "E6") (pinfunction "E6_E6") (pintype "bidirectional"))
    )
    (net (code "57") (name "N$87") (class "Default")
      (node (ref "U$9") (pin "E7") (pinfunction "E7_E7") (pintype "bidirectional"))
    )
    (net (code "58") (name "N$119") (class "Default")
      (node (ref "ARDUINO-MEGA") (pin "14-TX3") (pinfunction "14-TX3_14-TX3") (pintype "bidirectional"))
    )
    (net (code "59") (name "N$120") (class "Default")
      (node (ref "ARDUINO-MEGA") (pin "15-RX3") (pinfunction "15-RX3_15-RX3") (pintype "bidirectional"))
    )
    (net (code "60") (name "N$121") (class "Default")
      (node (ref "ARDUINO-MEGA") (pin "16-TX2") (pinfunction "16-TX2_16-TX2") (pintype "bidirectional"))
    )
    (net (code "61") (name "N$122") (class "Default")
      (node (ref "ARDUINO-MEGA") (pin "17-RX2") (pinfunction "17-RX2_17-RX2") (pintype "bidirectional"))
    )
    (net (code "62") (name "N$129") (class "Default")
      (node (ref "U$9") (pin "E9") (pinfunction "E9_E9") (pintype "bidirectional"))
    )
    (net (code "63") (name "N$130") (class "Default")
      (node (ref "U$9") (pin "E10") (pinfunction "E10_E10") (pintype "bidirectional"))
    )
    (net (code "64") (name "N$131") (class "Default")
      (node (ref "U$9") (pin "E11") (pinfunction "E11_E11") (pintype "bidirectional"))
    )
    (net (code "65") (name "N$132") (class "Default")
      (node (ref "U$9") (pin "E12") (pinfunction "E12_E12") (pintype "bidirectional"))
    )
    (net (code "66") (name "N$133") (class "Default")
      (node (ref "U$9") (pin "E13") (pinfunction "E13_E13") (pintype "bidirectional"))
    )
    (net (code "67") (name "Net-(5V-SOURCE-VIN)") (class "Default")
      (node (ref "5V-SOURCE") (pin "IN+") (pinfunction "VIN_IN+") (pintype "bidirectional"))
      (node (ref "MOTORS-SOURCE") (pin "IN+") (pinfunction "VIN_IN+") (pintype "bidirectional"))
      (node (ref "POWER-SW") (pin "P2") (pinfunction "2_P2") (pintype "passive"))
    )
    (net (code "68") (name "Net-(BC547-PadB)") (class "Default")
      (node (ref "BC547") (pin "B") (pinfunction "B_B") (pintype "passive"))
      (node (ref "R_BUZZ") (pin "2") (pinfunction "2_2") (pintype "passive"))
    )
    (net (code "69") (name "Net-(BUZZER-2)") (class "Default")
      (node (ref "BC547") (pin "C") (pinfunction "C_C") (pintype "passive"))
      (node (ref "BUZZER") (pin "-") (pinfunction "2_-") (pintype "passive"))
    )
    (net (code "70") (name "Net-(DS1-PadA)") (class "Default")
      (node (ref "DS1") (pin "A") (pinfunction "A_A") (pintype "passive"))
      (node (ref "SERVO_1") (pin "SIGNAL") (pinfunction "SIGNAL_SIGNAL") (pintype "bidirectional"))
    )
    (net (code "71") (name "Net-(DS2-PadA)") (class "Default")
      (node (ref "DS2") (pin "A") (pinfunction "A_A") (pintype "passive"))
      (node (ref "SERVO_2") (pin "SIGNAL") (pinfunction "SIGNAL_SIGNAL") (pintype "bidirectional"))
    )
    (net (code "72") (name "Net-(DS3-PadA)") (class "Default")
      (node (ref "DS3") (pin "A") (pinfunction "A_A") (pintype "passive"))
      (node (ref "SERVO_3") (pin "SIGNAL") (pinfunction "SIGNAL_SIGNAL") (pintype "bidirectional"))
    )
    (net (code "73") (name "Net-(DS4-PadA)") (class "Default")
      (node (ref "DS4") (pin "A") (pinfunction "A_A") (pintype "passive"))
      (node (ref "SERVO_4") (pin "SIGNAL") (pinfunction "SIGNAL_SIGNAL") (pintype "bidirectional"))
    )
    (net (code "74") (name "Net-(FAN1-PadVCC)") (class "Default")
      (node (ref "FAN1") (pin "VCC") (pinfunction "VCC_VCC") (pintype "bidirectional"))
      (node (ref "SW_FAN1") (pin "2") (pinfunction "2_2") (pintype "passive"))
    )
    (net (code "75") (name "Net-(FAN_AUX-PadVCC)") (class "Default")
      (node (ref "FAN_AUX") (pin "VCC") (pinfunction "VCC_VCC") (pintype "bidirectional"))
      (node (ref "SW_FAN_AUX") (pin "2") (pinfunction "2_2") (pintype "passive"))
    )
    (net (code "76") (name "Net-(LED-PWR-PadC)") (class "Default")
      (node (ref "LED-PWR") (pin "C") (pinfunction "C_C") (pintype "passive"))
      (node (ref "RLED-PWR") (pin "2") (pinfunction "2_2") (pintype "passive"))
    )
    (net (code "77") (name "Net-(LED1-PadC)") (class "Default")
      (node (ref "LED1") (pin "C") (pinfunction "C_C") (pintype "passive"))
      (node (ref "RLED-1") (pin "2") (pinfunction "2_2") (pintype "passive"))
    )
    (net (code "78") (name "Net-(LED2-PadC)") (class "Default")
      (node (ref "LED2") (pin "C") (pinfunction "C_C") (pintype "passive"))
      (node (ref "RLED-2") (pin "2") (pinfunction "2_2") (pintype "passive"))
    )
    (net (code "79") (name "Net-(LED3-PadC)") (class "Default")
      (node (ref "LED3") (pin "C") (pinfunction "C_C") (pintype "passive"))
      (node (ref "RLED-3") (pin "2") (pinfunction "2_2") (pintype "passive"))
    )
    (net (code "80") (name "Net-(LED4-PadC)") (class "Default")
      (node (ref "LED4") (pin "C") (pinfunction "C_C") (pintype "passive"))
      (node (ref "RLED-4") (pin "2") (pinfunction "2_2") (pintype "passive"))
    )
    (net (code "81") (name "Net-(LED5-PadC)") (class "Default")
      (node (ref "LED5") (pin "C") (pinfunction "C_C") (pintype "passive"))
      (node (ref "RLED-5") (pin "2") (pinfunction "2_2") (pintype "passive"))
    )
    (net (code "82") (name "Net-(U$23-7.4V)") (class "Default")
      (node (ref "POWER-SW") (pin "COM") (pinfunction "COM_COM") (pintype "passive"))
      (node (ref "U$23") (pin "VCC") (pinfunction "7.4V_VCC") (pintype "bidirectional"))
    )
    (net (code "83") (name "OUT1-MOTOR-LEFT") (class "Default")
      (node (ref "DRIVER-LEFT") (pin "AO1") (pinfunction "AO1_AO1") (pintype "bidirectional"))
      (node (ref "DRIVER-LEFT") (pin "BO1") (pinfunction "BO1_BO1") (pintype "bidirectional"))
      (node (ref "MOTOR_LEFT") (pin "OUTB") (pinfunction "OUTB_OUTB") (pintype "bidirectional"))
    )
    (net (code "84") (name "OUT1-MOTOR-RIGHT") (class "Default")
      (node (ref "DRIVER-RIGHT") (pin "AO1") (pinfunction "AO1_AO1") (pintype "bidirectional"))
      (node (ref "DRIVER-RIGHT") (pin "BO1") (pinfunction "BO1_BO1") (pintype "bidirectional"))
      (node (ref "MOTOR_RIGHT") (pin "OUTB") (pinfunction "OUTB_OUTB") (pintype "bidirectional"))
    )
    (net (code "85") (name "OUT2-MOTOR-LEFT") (class "Default")
      (node (ref "DRIVER-LEFT") (pin "AO2") (pinfunction "AO2_AO2") (pintype "bidirectional"))
      (node (ref "DRIVER-LEFT") (pin "BO2") (pinfunction "BO2_BO2") (pintype "bidirectional"))
      (node (ref "MOTOR_LEFT") (pin "OUTA") (pinfunction "OUTA_OUTA") (pintype "bidirectional"))
    )
    (net (code "86") (name "OUT2-MOTOR-RIGHT") (class "Default")
      (node (ref "DRIVER-RIGHT") (pin "AO2") (pinfunction "AO2_AO2") (pintype "bidirectional"))
      (node (ref "DRIVER-RIGHT") (pin "BO2") (pinfunction "BO2_BO2") (pintype "bidirectional"))
      (node (ref "MOTOR_RIGHT") (pin "OUTA") (pinfunction "OUTA_OUTA") (pintype "bidirectional"))
    )
    (net (code "87") (name "PUSH2") (class "Default")
      (node (ref "PUSH2") (pin "3") (pinfunction "P_3") (pintype "passive"))
      (node (ref "PUSH2") (pin "4") (pinfunction "P1_4") (pintype "passive"))
      (node (ref "RPUSH-2") (pin "2") (pinfunction "2_2") (pintype "passive"))
    )
    (net (code "88") (name "PUSH3") (class "Default")
      (node (ref "PUSH3") (pin "3") (pinfunction "P_3") (pintype "passive"))
      (node (ref "PUSH3") (pin "4") (pinfunction "P1_4") (pintype "passive"))
      (node (ref "R-PUSH3") (pin "2") (pinfunction "2_2") (pintype "passive"))
    )
    (net (code "89") (name "PUSH4") (class "Default")
      (node (ref "PUSH4") (pin "3") (pinfunction "P_3") (pintype "passive"))
      (node (ref "PUSH4") (pin "4") (pinfunction "P1_4") (pintype "passive"))
      (node (ref "RPUSH-4") (pin "2") (pinfunction "2_2") (pintype "passive"))
    )
    (net (code "90") (name "PWM-MOTOR-LEFT") (class "Default")
      (node (ref "DRIVER-LEFT") (pin "PWMA") (pinfunction "PWMA_PWMA") (pintype "bidirectional"))
      (node (ref "DRIVER-LEFT") (pin "PWMB") (pinfunction "PWMB_PWMB") (pintype "bidirectional"))
    )
    (net (code "91") (name "PWM-MOTOR-RIGHT") (class "Default")
      (node (ref "DRIVER-RIGHT") (pin "PWMA") (pinfunction "PWMA_PWMA") (pintype "bidirectional"))
      (node (ref "DRIVER-RIGHT") (pin "PWMB") (pinfunction "PWMB_PWMB") (pintype "bidirectional"))
    )
    (net (code "92") (name "RESET") (class "Default")
      (node (ref "ARDUINO-MEGA") (pin "RESET") (pinfunction "RESET_RESET") (pintype "bidirectional"))
      (node (ref "HC-05-PROG") (pin "RESET") (pinfunction "RESET_RESET") (pintype "bidirectional"))
      (node (ref "PUSH-RST") (pin "3") (pinfunction "P_3") (pintype "passive"))
      (node (ref "PUSH-RST") (pin "4") (pinfunction "P1_4") (pintype "passive"))
      (node (ref "U$14") (pin "RESET") (pinfunction "NC_4_RESET") (pintype "bidirectional"))
    )
    (net (code "93") (name "RX0") (class "Default")
      (node (ref "ARDUINO-MEGA") (pin "0-RX0") (pinfunction "0-RX0_0-RX0") (pintype "bidirectional"))
      (node (ref "HC-05-PROG") (pin "TXD") (pinfunction "TX_TXD") (pintype "bidirectional"))
      (node (ref "U$14") (pin "0-RX0") (pinfunction "NC_5_0-RX0") (pintype "bidirectional"))
    )
    (net (code "94") (name "SCD") (class "Default")
      (node (ref "LINE-SENSOR") (pin "SCD") (pinfunction "SCD_SCD") (pintype "bidirectional"))
    )
    (net (code "95") (name "SCI") (class "Default")
      (node (ref "LINE-SENSOR") (pin "SCI") (pinfunction "SCI_SCI") (pintype "bidirectional"))
    )
    (net (code "96") (name "SCL") (class "Default")
      (node (ref "ADXL335-ACELEROMETER") (pin "SCL") (pinfunction "SCL_SCL") (pintype "bidirectional"))
      (node (ref "ARDUINO-MEGA") (pin "SCL") (pinfunction "SCL_SCL") (pintype "bidirectional"))
    )
    (net (code "97") (name "SDA") (class "Default")
      (node (ref "ADXL335-ACELEROMETER") (pin "SDA") (pinfunction "SDA_SDA") (pintype "bidirectional"))
      (node (ref "ARDUINO-MEGA") (pin "SDA") (pinfunction "SDA_SDA") (pintype "bidirectional"))
    )
    (net (code "98") (name "SD_DI") (class "Default")
      (node (ref "ARDUINO-MEGA") (pin "11") (pinfunction "11_11") (pintype "bidirectional"))
      (node (ref "U$14") (pin "11") (pinfunction "SD_DI_11") (pintype "bidirectional"))
    )
    (net (code "99") (name "SD_DO") (class "Default")
      (node (ref "ARDUINO-MEGA") (pin "12") (pinfunction "12_12") (pintype "bidirectional"))
      (node (ref "U$14") (pin "12") (pinfunction "SD_DO_12") (pintype "bidirectional"))
    )
    (net (code "100") (name "SD_SCK") (class "Default")
      (node (ref "ARDUINO-MEGA") (pin "13") (pinfunction "13_13") (pintype "bidirectional"))
      (node (ref "U$14") (pin "13") (pinfunction "SD_SCK_13") (pintype "bidirectional"))
    )
    (net (code "101") (name "SD_SS") (class "Default")
      (node (ref "ARDUINO-MEGA") (pin "10") (pinfunction "10_10") (pintype "bidirectional"))
      (node (ref "U$14") (pin "10") (pinfunction "SD_SS_10") (pintype "bidirectional"))
    )
    (net (code "102") (name "SERVO1") (class "Default")
      (node (ref "DS1") (pin "C") (pinfunction "C_C") (pintype "passive"))
    )
    (net (code "103") (name "SERVO2") (class "Default")
      (node (ref "DS2") (pin "C") (pinfunction "C_C") (pintype "passive"))
    )
    (net (code "104") (name "SERVO3") (class "Default")
      (node (ref "DS3") (pin "C") (pinfunction "C_C") (pintype "passive"))
    )
    (net (code "105") (name "SERVO4") (class "Default")
      (node (ref "DS4") (pin "C") (pinfunction "C_C") (pintype "passive"))
    )
    (net (code "106") (name "SF") (class "Default")
      (node (ref "LINE-SENSOR") (pin "SF") (pinfunction "SF_SF") (pintype "bidirectional"))
    )
    (net (code "107") (name "SHARP-LEFT") (class "Default")
      (node (ref "SHARP-LEFT") (pin "DIST") (pinfunction "DISTANCE_DIST") (pintype "bidirectional"))
    )
    (net (code "108") (name "SHARP-MIDDLE") (class "Default")
      (node (ref "SHARP-MIDDLE") (pin "DIST") (pinfunction "DISTANCE_DIST") (pintype "bidirectional"))
    )
    (net (code "109") (name "SHARP-RIGHT") (class "Default")
      (node (ref "SHARP-RIGHT") (pin "DIST") (pinfunction "DISTANCE_DIST") (pintype "bidirectional"))
    )
    (net (code "110") (name "SID") (class "Default")
      (node (ref "LINE-SENSOR") (pin "SID") (pinfunction "SID_SID") (pintype "bidirectional"))
    )
    (net (code "111") (name "SII") (class "Default")
      (node (ref "LINE-SENSOR") (pin "SII") (pinfunction "SII_SII") (pintype "bidirectional"))
    )
    (net (code "112") (name "SOURCE") (class "Default")
      (node (ref "Q1") (pin "2") (pinfunction "S_2") (pintype "passive"))
    )
    (net (code "113") (name "SSD") (class "Default")
      (node (ref "LINE-SENSOR") (pin "SSD") (pinfunction "SSD_SSD") (pintype "bidirectional"))
    )
    (net (code "114") (name "SSI") (class "Default")
      (node (ref "LINE-SENSOR") (pin "SSI") (pinfunction "SSI_SSI") (pintype "bidirectional"))
    )
    (net (code "115") (name "TX0") (class "Default")
      (node (ref "ARDUINO-MEGA") (pin "1-TX0") (pinfunction "1-TX0_1-TX0") (pintype "bidirectional"))
      (node (ref "HC-05-PROG") (pin "RXD") (pinfunction "RX_RXD") (pintype "bidirectional"))
      (node (ref "U$14") (pin "1-TX0") (pinfunction "NC_6_1-TX0") (pintype "bidirectional"))
    )
    (net (code "116") (name "VCC") (class "Default")
      (node (ref "5V-SOURCE") (pin "OUT+") (pinfunction "VOUT_OUT+") (pintype "bidirectional"))
      (node (ref "ADXL335-ACELEROMETER") (pin "VCC") (pinfunction "VCC_VCC") (pintype "bidirectional"))
      (node (ref "ARDUINO-MEGA") (pin "5V_1") (pinfunction "5V_1_5V_1") (pintype "bidirectional"))
      (node (ref "BUZZER") (pin "+") (pinfunction "1_+") (pintype "passive"))
      (node (ref "DIPSW") (pin "5") (pinfunction "5_5") (pintype "passive"))
      (node (ref "DIPSW") (pin "6") (pinfunction "6_6") (pintype "passive"))
      (node (ref "DIPSW") (pin "7") (pinfunction "7_7") (pintype "passive"))
      (node (ref "DIPSW") (pin "8") (pinfunction "8_8") (pintype "passive"))
      (node (ref "DRIVER-LEFT") (pin "VCC") (pinfunction "VCC_VCC") (pintype "bidirectional"))
      (node (ref "DRIVER-RIGHT") (pin "VCC") (pinfunction "VCC_VCC") (pintype "bidirectional"))
      (node (ref "HC-05-PROG") (pin "VCC") (pinfunction "VCC_VCC") (pintype "bidirectional"))
      (node (ref "LED-PWR") (pin "A") (pinfunction "A_A") (pintype "passive"))
      (node (ref "LINE-SENSOR") (pin "VCC") (pinfunction "VCC_VCC") (pintype "bidirectional"))
      (node (ref "MOTOR_LEFT") (pin "VCC") (pinfunction "VCC_VCC") (pintype "bidirectional"))
      (node (ref "MOTOR_RIGHT") (pin "VCC") (pinfunction "VCC_VCC") (pintype "bidirectional"))
      (node (ref "PUSH-RST") (pin "1") (pinfunction "S_1") (pintype "passive"))
      (node (ref "PUSH2") (pin "1") (pinfunction "S_1") (pintype "passive"))
      (node (ref "PUSH3") (pin "1") (pinfunction "S_1") (pintype "passive"))
      (node (ref "PUSH4") (pin "1") (pinfunction "S_1") (pintype "passive"))
      (node (ref "SERVO_1") (pin "VCC") (pinfunction "VCC_VCC") (pintype "bidirectional"))
      (node (ref "SERVO_2") (pin "VCC") (pinfunction "VCC_VCC") (pintype "bidirectional"))
      (node (ref "SERVO_3") (pin "VCC") (pinfunction "VCC_VCC") (pintype "bidirectional"))
      (node (ref "SERVO_4") (pin "VCC") (pinfunction "VCC_VCC") (pintype "bidirectional"))
      (node (ref "SHARP-LEFT") (pin "VCC") (pinfunction "VCC_VCC") (pintype "bidirectional"))
      (node (ref "SHARP-MIDDLE") (pin "VCC") (pinfunction "VCC_VCC") (pintype "bidirectional"))
      (node (ref "SHARP-RIGHT") (pin "VCC") (pinfunction "VCC_VCC") (pintype "bidirectional"))
      (node (ref "SW_FAN1") (pin "1") (pinfunction "1_1") (pintype "passive"))
      (node (ref "SW_FAN_AUX") (pin "1") (pinfunction "1_1") (pintype "passive"))
      (node (ref "U$14") (pin "5V_1") (pinfunction "5V_5V_1") (pintype "bidirectional"))
      (node (ref "U$9") (pin "VCC") (pinfunction "VCC_VCC") (pintype "bidirectional"))
    )
    (net (code "117") (name "VIN") (class "Default")
      (node (ref "ARDUINO-MEGA") (pin "VIN") (pinfunction "VIN_VIN") (pintype "bidirectional"))
      (node (ref "U$14") (pin "VIN") (pinfunction "NC_2_VIN") (pintype "bidirectional"))
    )
    (net (code "118") (name "unconnected-(ARDUINO-MEGA-Pad5V_2)") (class "Default")
      (node (ref "ARDUINO-MEGA") (pin "5V_2") (pinfunction "5V_2_5V_2") (pintype "bidirectional"))
    )
    (net (code "119") (name "unconnected-(ARDUINO-MEGA-Pad5V_3)") (class "Default")
      (node (ref "ARDUINO-MEGA") (pin "5V_3") (pinfunction "5V_3_5V_3") (pintype "bidirectional"))
    )
    (net (code "120") (name "unconnected-(ARDUINO-MEGA-Pad22)") (class "Default")
      (node (ref "ARDUINO-MEGA") (pin "22") (pinfunction "22_22") (pintype "bidirectional"))
    )
    (net (code "121") (name "unconnected-(ARDUINO-MEGA-Pad23)") (class "Default")
      (node (ref "ARDUINO-MEGA") (pin "23") (pinfunction "23_23") (pintype "bidirectional"))
    )
    (net (code "122") (name "unconnected-(ARDUINO-MEGA-Pad24)") (class "Default")
      (node (ref "ARDUINO-MEGA") (pin "24") (pinfunction "24_24") (pintype "bidirectional"))
    )
    (net (code "123") (name "unconnected-(ARDUINO-MEGA-Pad25)") (class "Default")
      (node (ref "ARDUINO-MEGA") (pin "25") (pinfunction "25_25") (pintype "bidirectional"))
    )
    (net (code "124") (name "unconnected-(ARDUINO-MEGA-Pad26)") (class "Default")
      (node (ref "ARDUINO-MEGA") (pin "26") (pinfunction "26_26") (pintype "bidirectional"))
    )
    (net (code "125") (name "unconnected-(ARDUINO-MEGA-Pad27)") (class "Default")
      (node (ref "ARDUINO-MEGA") (pin "27") (pinfunction "27_27") (pintype "bidirectional"))
    )
    (net (code "126") (name "unconnected-(ARDUINO-MEGA-Pad28)") (class "Default")
      (node (ref "ARDUINO-MEGA") (pin "28") (pinfunction "28_28") (pintype "bidirectional"))
    )
    (net (code "127") (name "unconnected-(ARDUINO-MEGA-Pad29)") (class "Default")
      (node (ref "ARDUINO-MEGA") (pin "29") (pinfunction "29_29") (pintype "bidirectional"))
    )
    (net (code "128") (name "unconnected-(ARDUINO-MEGA-Pad30)") (class "Default")
      (node (ref "ARDUINO-MEGA") (pin "30") (pinfunction "30_30") (pintype "bidirectional"))
    )
    (net (code "129") (name "unconnected-(ARDUINO-MEGA-Pad31)") (class "Default")
      (node (ref "ARDUINO-MEGA") (pin "31") (pinfunction "31_31") (pintype "bidirectional"))
    )
    (net (code "130") (name "unconnected-(ARDUINO-MEGA-Pad32)") (class "Default")
      (node (ref "ARDUINO-MEGA") (pin "32") (pinfunction "32_32") (pintype "bidirectional"))
    )
    (net (code "131") (name "unconnected-(ARDUINO-MEGA-Pad33)") (class "Default")
      (node (ref "ARDUINO-MEGA") (pin "33") (pinfunction "33_33") (pintype "bidirectional"))
    )
    (net (code "132") (name "unconnected-(ARDUINO-MEGA-Pad34)") (class "Default")
      (node (ref "ARDUINO-MEGA") (pin "34") (pinfunction "34_34") (pintype "bidirectional"))
    )
    (net (code "133") (name "unconnected-(ARDUINO-MEGA-Pad35)") (class "Default")
      (node (ref "ARDUINO-MEGA") (pin "35") (pinfunction "35_35") (pintype "bidirectional"))
    )
    (net (code "134") (name "unconnected-(ARDUINO-MEGA-Pad36)") (class "Default")
      (node (ref "ARDUINO-MEGA") (pin "36") (pinfunction "36_36") (pintype "bidirectional"))
    )
    (net (code "135") (name "unconnected-(ARDUINO-MEGA-Pad37)") (class "Default")
      (node (ref "ARDUINO-MEGA") (pin "37") (pinfunction "37_37") (pintype "bidirectional"))
    )
    (net (code "136") (name "unconnected-(ARDUINO-MEGA-Pad38)") (class "Default")
      (node (ref "ARDUINO-MEGA") (pin "38") (pinfunction "38_38") (pintype "bidirectional"))
    )
    (net (code "137") (name "unconnected-(ARDUINO-MEGA-Pad39)") (class "Default")
      (node (ref "ARDUINO-MEGA") (pin "39") (pinfunction "39_39") (pintype "bidirectional"))
    )
    (net (code "138") (name "unconnected-(ARDUINO-MEGA-Pad40)") (class "Default")
      (node (ref "ARDUINO-MEGA") (pin "40") (pinfunction "40_40") (pintype "bidirectional"))
    )
    (net (code "139") (name "unconnected-(ARDUINO-MEGA-Pad41)") (class "Default")
      (node (ref "ARDUINO-MEGA") (pin "41") (pinfunction "41_41") (pintype "bidirectional"))
    )
    (net (code "140") (name "unconnected-(ARDUINO-MEGA-Pad42)") (class "Default")
      (node (ref "ARDUINO-MEGA") (pin "42") (pinfunction "42_42") (pintype "bidirectional"))
    )
    (net (code "141") (name "unconnected-(ARDUINO-MEGA-Pad43)") (class "Default")
      (node (ref "ARDUINO-MEGA") (pin "43") (pinfunction "43_43") (pintype "bidirectional"))
    )
    (net (code "142") (name "unconnected-(ARDUINO-MEGA-Pad44)") (class "Default")
      (node (ref "ARDUINO-MEGA") (pin "44") (pinfunction "44_44") (pintype "bidirectional"))
    )
    (net (code "143") (name "unconnected-(ARDUINO-MEGA-Pad45)") (class "Default")
      (node (ref "ARDUINO-MEGA") (pin "45") (pinfunction "45_45") (pintype "bidirectional"))
    )
    (net (code "144") (name "unconnected-(ARDUINO-MEGA-Pad46)") (class "Default")
      (node (ref "ARDUINO-MEGA") (pin "46") (pinfunction "46_46") (pintype "bidirectional"))
    )
    (net (code "145") (name "unconnected-(ARDUINO-MEGA-Pad47)") (class "Default")
      (node (ref "ARDUINO-MEGA") (pin "47") (pinfunction "47_47") (pintype "bidirectional"))
    )
    (net (code "146") (name "unconnected-(ARDUINO-MEGA-Pad48)") (class "Default")
      (node (ref "ARDUINO-MEGA") (pin "48") (pinfunction "48_48") (pintype "bidirectional"))
    )
    (net (code "147") (name "unconnected-(ARDUINO-MEGA-Pad49)") (class "Default")
      (node (ref "ARDUINO-MEGA") (pin "49") (pinfunction "49_49") (pintype "bidirectional"))
    )
    (net (code "148") (name "unconnected-(ARDUINO-MEGA-Pad50)") (class "Default")
      (node (ref "ARDUINO-MEGA") (pin "50") (pinfunction "50_50") (pintype "bidirectional"))
    )
    (net (code "149") (name "unconnected-(ARDUINO-MEGA-Pad51)") (class "Default")
      (node (ref "ARDUINO-MEGA") (pin "51") (pinfunction "51_51") (pintype "bidirectional"))
    )
    (net (code "150") (name "unconnected-(ARDUINO-MEGA-Pad52)") (class "Default")
      (node (ref "ARDUINO-MEGA") (pin "52") (pinfunction "52_52") (pintype "bidirectional"))
    )
    (net (code "151") (name "unconnected-(ARDUINO-MEGA-Pad53)") (class "Default")
      (node (ref "ARDUINO-MEGA") (pin "53") (pinfunction "53_53") (pintype "bidirectional"))
    )
    (net (code "152") (name "unconnected-(ARDUINO-MEGA-PadGND_3)") (class "Default")
      (node (ref "ARDUINO-MEGA") (pin "GND_3") (pinfunction "GND_3_GND_3") (pintype "bidirectional"))
    )
    (net (code "153") (name "unconnected-(ARDUINO-MEGA-PadGND_4)") (class "Default")
      (node (ref "ARDUINO-MEGA") (pin "GND_4") (pinfunction "GND_4_GND_4") (pintype "bidirectional"))
    )
    (net (code "154") (name "unconnected-(ARDUINO-MEGA-PadIOREF)") (class "Default")
      (node (ref "ARDUINO-MEGA") (pin "IOREF") (pinfunction "IOREF_IOREF") (pintype "bidirectional"))
    )
    (net (code "155") (name "unconnected-(ARDUINO-MEGA-PadNC)") (class "Default")
      (node (ref "ARDUINO-MEGA") (pin "NC") (pinfunction "NC_NC") (pintype "bidirectional"))
    )
    (net (code "156") (name "unconnected-(DRIVER-LEFT-PadSTBY)") (class "Default")
      (node (ref "DRIVER-LEFT") (pin "STBY") (pinfunction "STBY_STBY") (pintype "bidirectional"))
    )
    (net (code "157") (name "unconnected-(DRIVER-RIGHT-PadSTBY)") (class "Default")
      (node (ref "DRIVER-RIGHT") (pin "STBY") (pinfunction "STBY_STBY") (pintype "bidirectional"))
    )
    (net (code "158") (name "unconnected-(LED_1W-A-Pad1)") (class "Default")
      (node (ref "LED_1W") (pin "1") (pinfunction "A_1") (pintype "passive"))
    )
    (net (code "159") (name "unconnected-(LED_1W-C-Pad2)") (class "Default")
      (node (ref "LED_1W") (pin "2") (pinfunction "C_2") (pintype "passive"))
    )
    (net (code "160") (name "unconnected-(POWER-SW-1-PadP1)") (class "Default")
      (node (ref "POWER-SW") (pin "P1") (pinfunction "1_P1") (pintype "passive"))
    )
    (net (code "161") (name "unconnected-(PUSH-RST-S1-Pad2)") (class "Default")
      (node (ref "PUSH-RST") (pin "2") (pinfunction "S1_2") (pintype "passive"))
    )
    (net (code "162") (name "unconnected-(PUSH2-S1-Pad2)") (class "Default")
      (node (ref "PUSH2") (pin "2") (pinfunction "S1_2") (pintype "passive"))
    )
    (net (code "163") (name "unconnected-(PUSH3-S1-Pad2)") (class "Default")
      (node (ref "PUSH3") (pin "2") (pinfunction "S1_2") (pintype "passive"))
    )
    (net (code "164") (name "unconnected-(PUSH4-S1-Pad2)") (class "Default")
      (node (ref "PUSH4") (pin "2") (pinfunction "S1_2") (pintype "passive"))
    )
    (net (code "165") (name "unconnected-(U$9-PadE8)") (class "Default")
      (node (ref "U$9") (pin "E8") (pinfunction "E8_E8") (pintype "bidirectional"))
    )
  )
)
